# POWER.net
KiCad netlist of a schematic drawn in Altium Designer
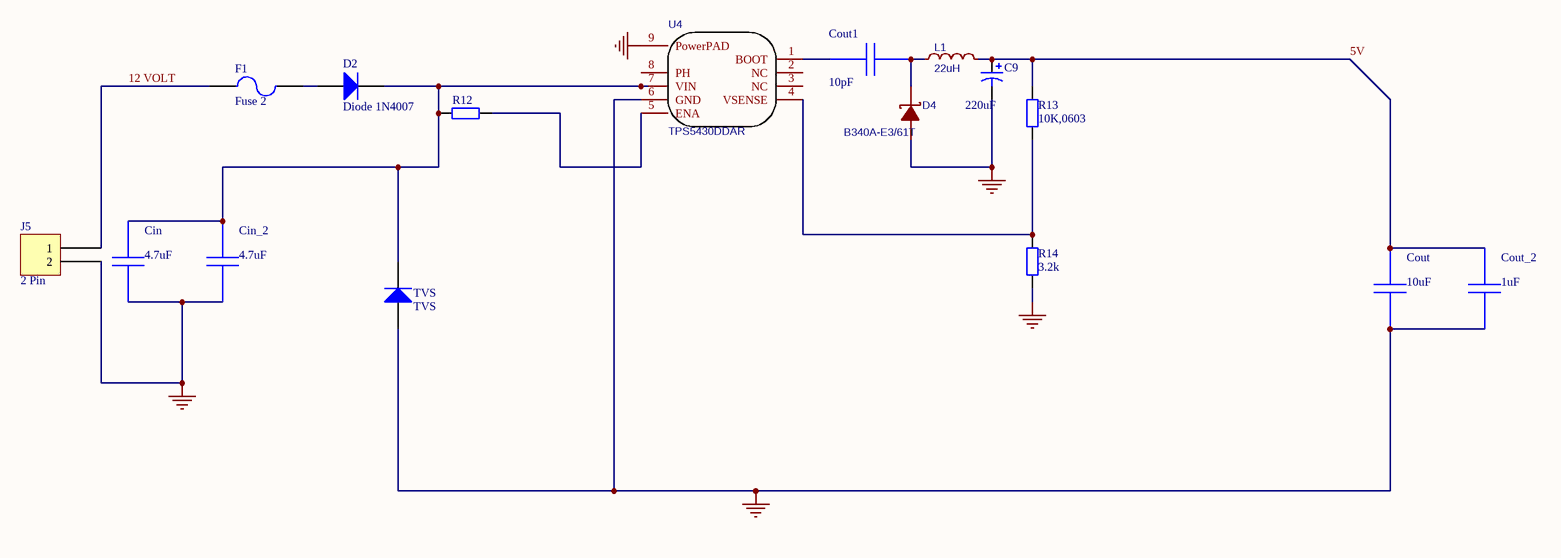
[diagram p0: POWER.schdoc]

(export (version "E")
  (design (tool "Eeschema 10.0.6"))
  (components
    (comp (ref "C9")
      (value "220uF")
      (footprint "1206")
      (description "Polarized Capacitor (Surface Mount)")
      (fields (field (name "Comment") "Cap Pol3") (field (name "PUBLISHER") "Altium Limited"))
      (libsource (lib "Miscellaneous Devices") (part "Cap Pol3"))
    )
    (comp (ref "Cin")
      (value "4.7uF")
      (footprint "1206")
      (description "GRM32ER71J106KA1")
      (fields (field (name "MANUFACTURER PART NUMBER") "GRM32ER71J106KA12L"))
      (libsource (lib "TI WEBENCH") (part "Cin"))
    )
    (comp (ref "Cin_2")
      (value "4.7uF")
      (footprint "1206")
      (description "GRM32ER71J106KA1")
      (fields (field (name "MANUFACTURER PART NUMBER") "GRM32ER71J106KA12L"))
      (libsource (lib "TI WEBENCH") (part "Cin_2"))
    )
    (comp (ref "Cout")
      (value "10uF")
      (footprint "1206")
      (description "C1608X5R1A226M08")
      (fields (field (name "MANUFACTURER PART NUMBER") "C1608X5R1A226M080AC"))
      (libsource (lib "TI WEBENCH") (part "Cout"))
    )
    (comp (ref "Cout1")
      (value "10pF")
      (footprint "1206")
      (description "C1608X5R1A226M08")
      (fields (field (name "MANUFACTURER PART NUMBER") "C1608X5R1A226M080AC"))
      (libsource (lib "TI WEBENCH") (part "Cout"))
    )
    (comp (ref "Cout_2")
      (value "1uF")
      (footprint "1206")
      (description "C1608X5R1A226M08")
      (fields (field (name "MANUFACTURER PART NUMBER") "C1608X5R1A226M080AC"))
      (libsource (lib "TI WEBENCH") (part "Cout_2"))
    )
    (comp (ref "D2")
      (value "Diode 1N4007")
      (footprint "SMA(DO-214AC)")
      (description "1 Amp General Purpose Rectifier")
      (fields (field (name "PUBLISHER") "Altium Limited"))
      (libsource (lib "Miscellaneous Devices") (part "Diode 1N4007"))
    )
    (comp (ref "D4")
      (value "B340A-E3/61T")
      (footprint "SMA(DO-214AC)")
      (fields (field (name "BOM_SUPPLIER PART") "C15570"))
      (libsource (lib "Proje01") (part "B340A-E3/61T"))
    )
    (comp (ref "F1")
      (value "Fuse 2")
      (footprint "1206")
      (description "Fuse")
      (fields (field (name "PUBLISHER") "Altium Limited"))
      (libsource (lib "Miscellaneous Devices") (part "Fuse 2"))
    )
    (comp (ref "J5") (value "2 Pin") (footprint "HDR1X2") (libsource (lib "Connectors") (part "2 Pin")))
    (comp (ref "L1")
      (value "22uH")
      (footprint "l7070")
      (fields
        (field (name "BOM_SUPPLIER PART") "C304294")
        (field (name "BOM_MANUFACTURER PART") "NLV32T-150J-PF")
        (field (name "CONTRIBUTOR") "LCSC")
      )
      (libsource (lib "Proje01") (part "100uH"))
    )
    (comp (ref "R12")
      (value "~")
      (footprint "0805")
      (description "Resistor")
      (fields (field (name "PUBLISHER") "Altium Limited"))
      (libsource (lib "") (part "Res2_1"))
    )
    (comp (ref "R13")
      (value "10K,0603")
      (footprint "0805")
      (description "Resistor")
      (fields (field (name "PUBLISHER") "Altium Limited"))
      (libsource (lib "Proje01") (part "Res2"))
    )
    (comp (ref "R14")
      (value "3.2k")
      (footprint "0805")
      (description "Resistor")
      (fields (field (name "PUBLISHER") "Altium Limited"))
      (libsource (lib "Proje01") (part "Res2"))
    )
    (comp (ref "TVS")
      (value "TVS")
      (footprint "SMA(DO-214AC)")
      (description "1 Amp General Purpose Rectifier")
      (fields (field (name "PUBLISHER") "Altium Limited"))
      (libsource (lib "Miscellaneous Devices") (part "Diode 1N4007"))
    )
    (comp (ref "U4")
      (value "TPS5430DDAR")
      (footprint "SOP-8_EP_150MIL")
      (fields (field (name "BOM_SUPPLIER PART") "C9864"))
      (libsource (lib "Proje01") (part "TPS5430DDAR"))
    )
  )
  (nets
    (net (code "1") (name "/5V") (class "Default")
      (node (ref "C9") (pin "1") (pinfunction "1_1") (pintype "passive"))
      (node (ref "Cout") (pin "1") (pinfunction "1_1") (pintype "passive"))
      (node (ref "Cout_2") (pin "1") (pinfunction "1_1") (pintype "passive"))
      (node (ref "L1") (pin "2") (pinfunction "2_2") (pintype "passive"))
      (node (ref "R13") (pin "2") (pinfunction "2_2") (pintype "passive"))
    )
    (net (code "2") (name "/12 VOLT") (class "Default")
      (node (ref "F1") (pin "1") (pinfunction "1_1") (pintype "passive"))
      (node (ref "J5") (pin "1") (pinfunction "1_1") (pintype "passive"))
    )
    (net (code "3") (name "0") (class "Default")
      (node (ref "C9") (pin "2") (pinfunction "2_2") (pintype "passive"))
      (node (ref "Cin") (pin "2") (pinfunction "2_2") (pintype "passive"))
      (node (ref "Cin_2") (pin "2") (pinfunction "2_2") (pintype "passive"))
      (node (ref "Cout") (pin "2") (pinfunction "2_2") (pintype "passive"))
      (node (ref "Cout_2") (pin "2") (pinfunction "2_2") (pintype "passive"))
      (node (ref "D4") (pin "1") (pinfunction "A_1") (pintype "passive"))
      (node (ref "J5") (pin "2") (pinfunction "2_2") (pintype "passive"))
      (node (ref "R14") (pin "1") (pinfunction "1_1") (pintype "passive"))
      (node (ref "TVS") (pin "1") (pinfunction "A_1") (pintype "passive"))
      (node (ref "U4") (pin "6") (pinfunction "GND_6") (pintype "passive"))
      (node (ref "U4") (pin "9") (pinfunction "PowerPAD_9") (pintype "passive"))
    )
    (net (code "4") (name "Net-(D2-A)") (class "Default")
      (node (ref "D2") (pin "1") (pinfunction "A_1") (pintype "passive"))
      (node (ref "F1") (pin "2") (pinfunction "2_2") (pintype "passive"))
    )
    (net (code "5") (name "Net-(D2-K)") (class "Default")
      (node (ref "Cin") (pin "1") (pinfunction "1_1") (pintype "passive"))
      (node (ref "Cin_2") (pin "1") (pinfunction "1_1") (pintype "passive"))
      (node (ref "D2") (pin "2") (pinfunction "K_2") (pintype "passive"))
      (node (ref "R12") (pin "2") (pinfunction "2_2") (pintype "passive"))
      (node (ref "TVS") (pin "2") (pinfunction "K_2") (pintype "passive"))
      (node (ref "U4") (pin "7") (pinfunction "VIN_7") (pintype "passive"))
    )
    (net (code "6") (name "Net-(D4-K)") (class "Default")
      (node (ref "Cout1") (pin "2") (pinfunction "2_2") (pintype "passive"))
      (node (ref "D4") (pin "2") (pinfunction "K_2") (pintype "passive"))
      (node (ref "L1") (pin "1") (pinfunction "1_1") (pintype "passive"))
    )
    (net (code "7") (name "Net-(U4-BOOT)") (class "Default")
      (node (ref "Cout1") (pin "1") (pinfunction "1_1") (pintype "passive"))
      (node (ref "U4") (pin "1") (pinfunction "BOOT_1") (pintype "passive"))
    )
    (net (code "8") (name "Net-(U4-ENA)") (class "Default")
      (node (ref "R12") (pin "1") (pinfunction "1_1") (pintype "passive"))
      (node (ref "U4") (pin "5") (pinfunction "ENA_5") (pintype "passive"))
    )
    (net (code "9") (name "Net-(U4-VSENSE)") (class "Default")
      (node (ref "R13") (pin "1") (pinfunction "1_1") (pintype "passive"))
      (node (ref "R14") (pin "2") (pinfunction "2_2") (pintype "passive"))
      (node (ref "U4") (pin "4") (pinfunction "VSENSE_4") (pintype "passive"))
    )
    (net (code "10") (name "unconnected-(U4-NC-Pad2)") (class "Default")
      (node (ref "U4") (pin "2") (pinfunction "NC_2") (pintype "passive"))
    )
    (net (code "11") (name "unconnected-(U4-NC-Pad3)") (class "Default")
      (node (ref "U4") (pin "3") (pinfunction "NC_3") (pintype "passive"))
    )
    (net (code "12") (name "unconnected-(U4-PH-Pad8)") (class "Default")
      (node (ref "U4") (pin "8") (pinfunction "PH_8") (pintype "passive"))
    )
  )
)
